# xr_vco_components_preroute3.net
KiCad netlist of a schematic drawn in EAGLE
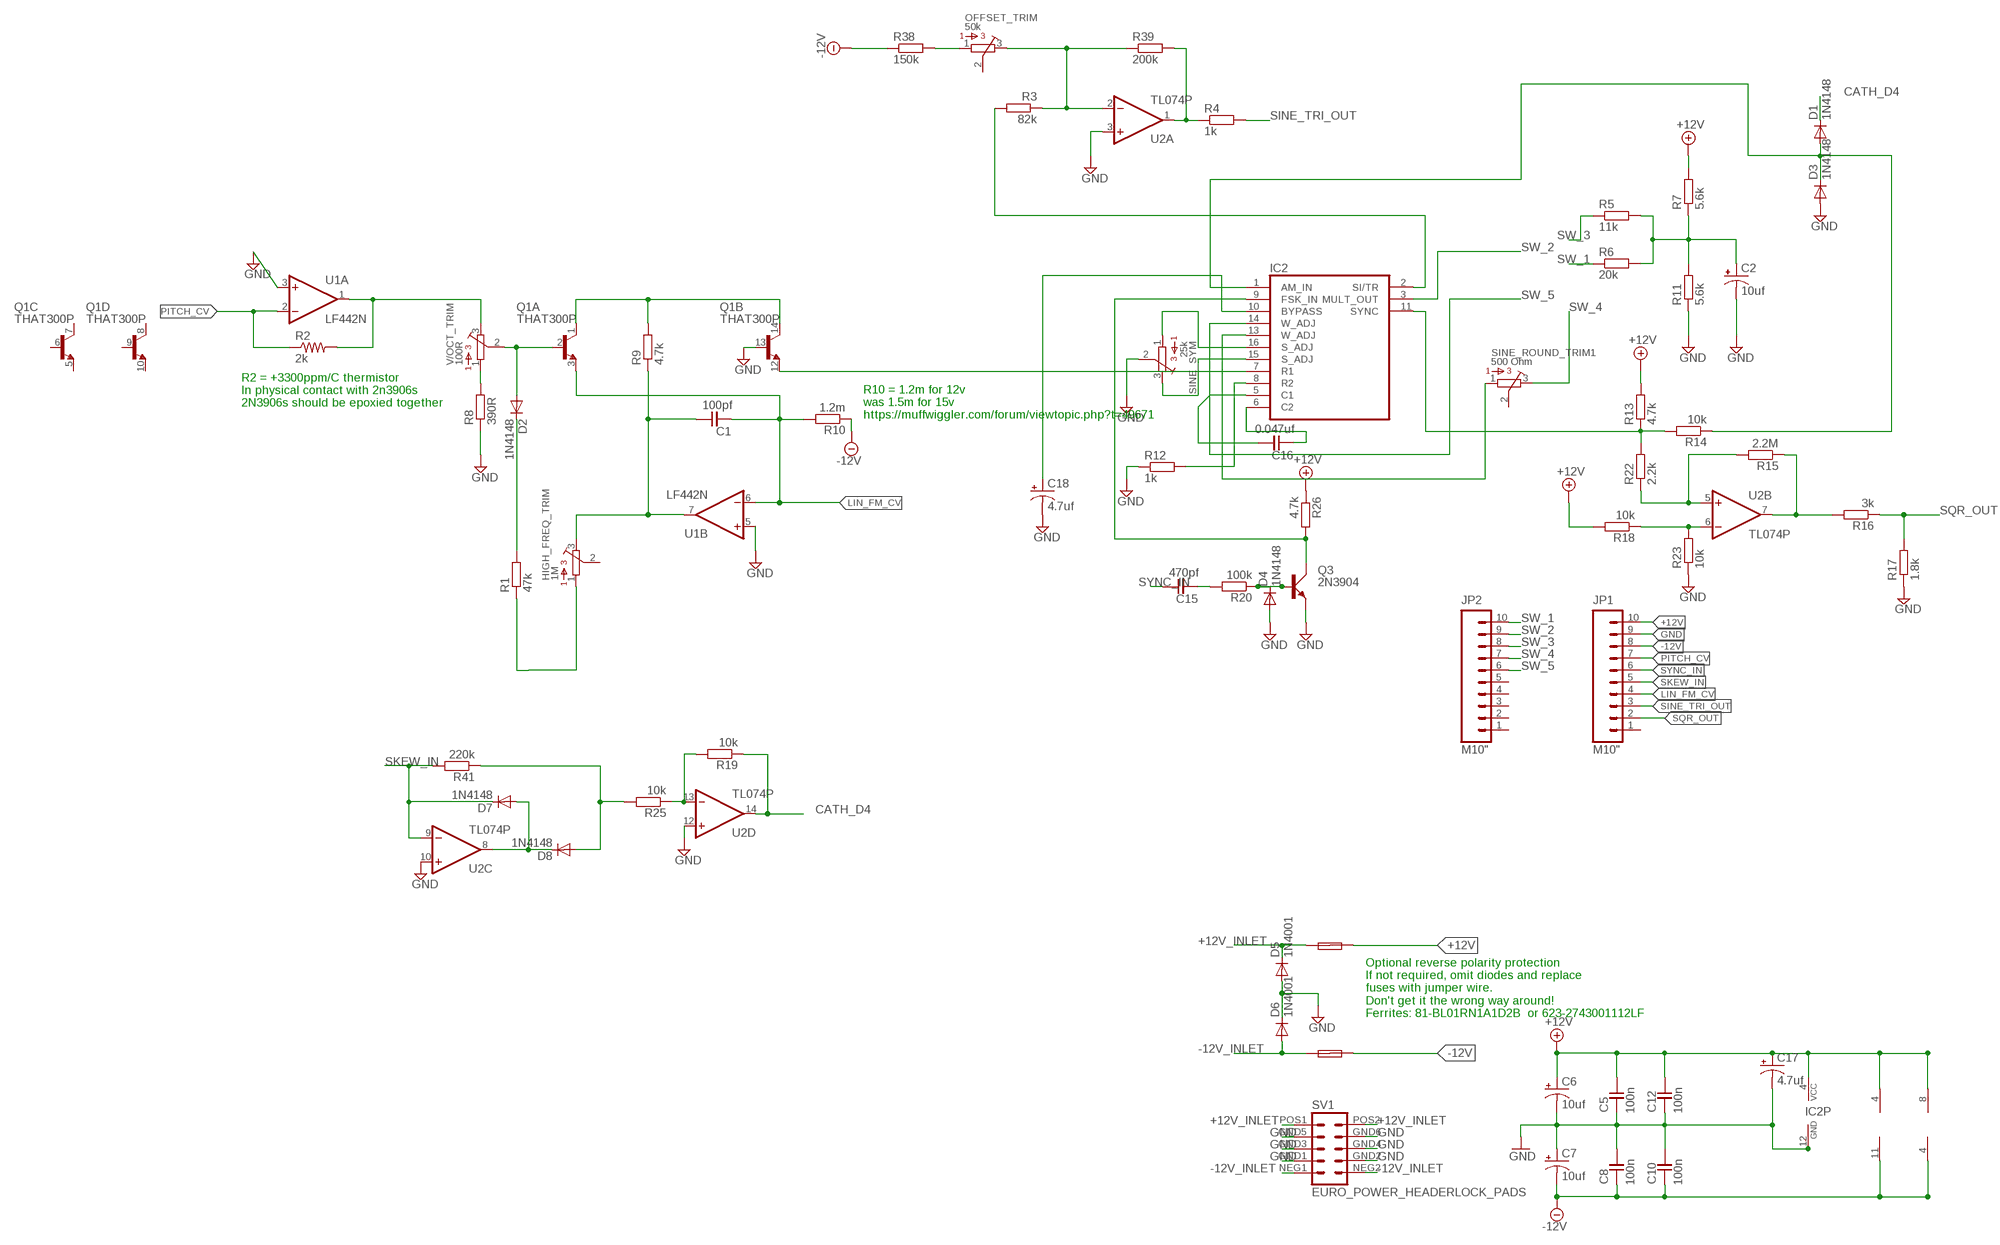
[diagram p0: schematic, sheet 1]

(export (version "E")
  (design (tool "Eeschema 10.0.6"))
  (components
    (comp (ref "C1")
      (value "100pf")
      (footprint "eagle-import:C050-024X044")
      (libsource (lib "eagle-import") (part "C-EU050-024X044"))
    )
    (comp (ref "C2")
      (value "10uf")
      (footprint "eagle-import:CPOL-RADIAL-10UF-25V")
      (libsource (lib "eagle-import") (part "CAP_POLPTH2"))
    )
    (comp (ref "C5")
      (value "100n")
      (footprint "eagle-import:C050-024X044")
      (libsource (lib "eagle-import") (part "C-EU050-024X044"))
    )
    (comp (ref "C6")
      (value "10uf")
      (footprint "eagle-import:CPOL-RADIAL-10UF-25V")
      (libsource (lib "eagle-import") (part "CAP_POLPTH2"))
    )
    (comp (ref "C7")
      (value "10uf")
      (footprint "eagle-import:CPOL-RADIAL-10UF-25V")
      (libsource (lib "eagle-import") (part "CAP_POLPTH2"))
    )
    (comp (ref "C8")
      (value "100n")
      (footprint "eagle-import:C050-024X044")
      (libsource (lib "eagle-import") (part "C-EU050-024X044"))
    )
    (comp (ref "C10")
      (value "100n")
      (footprint "eagle-import:C050-024X044")
      (libsource (lib "eagle-import") (part "C-EU050-024X044"))
    )
    (comp (ref "C12")
      (value "100n")
      (footprint "eagle-import:C050-024X044")
      (libsource (lib "eagle-import") (part "C-EU050-024X044"))
    )
    (comp (ref "C15")
      (value "470pf")
      (footprint "eagle-import:C050-024X044")
      (libsource (lib "eagle-import") (part "C-EU050-024X044"))
    )
    (comp (ref "C16")
      (value "0.047uf")
      (footprint "eagle-import:C050-024X044")
      (libsource (lib "eagle-import") (part "C-EU050-024X044"))
    )
    (comp (ref "C17")
      (value "4.7uf")
      (footprint "eagle-import:CPOL-RADIAL-10UF-25V")
      (libsource (lib "eagle-import") (part "CAP_POLPTH2"))
    )
    (comp (ref "C18")
      (value "4.7uf")
      (footprint "eagle-import:CPOL-RADIAL-10UF-25V")
      (libsource (lib "eagle-import") (part "CAP_POLPTH2"))
    )
    (comp (ref "D1")
      (value "1N4148")
      (footprint "eagle-import:DO35-7")
      (libsource (lib "eagle-import") (part "SMALL_DIODEDO35-7"))
    )
    (comp (ref "D2")
      (value "1N4148")
      (footprint "eagle-import:DO35-7")
      (libsource (lib "eagle-import") (part "SMALL_DIODEDO35-7"))
    )
    (comp (ref "D3")
      (value "1N4148")
      (footprint "eagle-import:DO35-7")
      (libsource (lib "eagle-import") (part "SMALL_DIODEDO35-7"))
    )
    (comp (ref "D4")
      (value "1N4148")
      (footprint "eagle-import:DO35-7")
      (libsource (lib "eagle-import") (part "SMALL_DIODEDO35-7"))
    )
    (comp (ref "D5")
      (value "1N4001")
      (footprint "eagle-import:DO41-10")
      (libsource (lib "eagle-import") (part "1N4004"))
    )
    (comp (ref "D6")
      (value "1N4001")
      (footprint "eagle-import:DO41-10")
      (libsource (lib "eagle-import") (part "1N4004"))
    )
    (comp (ref "D7")
      (value "1N4148")
      (footprint "eagle-import:DO35-7")
      (libsource (lib "eagle-import") (part "SMALL_DIODEDO35-7"))
    )
    (comp (ref "D8")
      (value "1N4148")
      (footprint "eagle-import:DO35-7")
      (libsource (lib "eagle-import") (part "SMALL_DIODEDO35-7"))
    )
    (comp (ref "F1")
      (value "FUSE")
      (footprint "eagle-import:C050H075X075")
      (libsource (lib "eagle-import") (part "PTC_FUSEPOLY_FUSE"))
    )
    (comp (ref "F2")
      (value "FUSE")
      (footprint "eagle-import:C050H075X075")
      (libsource (lib "eagle-import") (part "PTC_FUSEPOLY_FUSE"))
    )
    (comp (ref "HIGH_FREQ_TRIM")
      (value "1M")
      (footprint "eagle-import:BOURNS_3362P_TRIMMER")
      (libsource (lib "eagle-import") (part "BOURNS_3362P_TRIMMERP"))
    )
    (comp (ref "IC2")
      (value "XR-2206")
      (footprint "eagle-import:DIL16")
      (libsource (lib "eagle-import") (part "XR-2206"))
    )
    (comp (ref "JP1")
      (value "M10\"")
      (footprint "eagle-import:1X10")
      (libsource (lib "eagle-import") (part "M10{dblquote}"))
    )
    (comp (ref "JP2")
      (value "M10\"")
      (footprint "eagle-import:1X10")
      (libsource (lib "eagle-import") (part "M10{dblquote}"))
    )
    (comp (ref "OFFSET_TRIM")
      (value "50k")
      (footprint "eagle-import:BOURNS_3362P_TRIMMER")
      (libsource (lib "eagle-import") (part "BOURNS_3362P_TRIMMERP"))
    )
    (comp (ref "Q1")
      (value "THAT300P")
      (footprint "eagle-import:DIL14")
      (libsource (lib "eagle-import") (part "THAT300P"))
    )
    (comp (ref "Q3")
      (value "2N3904")
      (footprint "eagle-import:TO92D")
      (libsource (lib "eagle-import") (part "2N3904"))
    )
    (comp (ref "R1")
      (value "47k")
      (footprint "eagle-import:7MM_RESISTOR")
      (libsource (lib "eagle-import") (part "RESISTOR7MM"))
    )
    (comp (ref "R2")
      (value "2k")
      (footprint "eagle-import:0309_12")
      (libsource (lib "eagle-import") (part "R-US_0309/12"))
    )
    (comp (ref "R3")
      (value "82k")
      (footprint "eagle-import:7MM_RESISTOR")
      (libsource (lib "eagle-import") (part "RESISTOR7MM"))
    )
    (comp (ref "R4")
      (value "1k")
      (footprint "eagle-import:7MM_RESISTOR")
      (libsource (lib "eagle-import") (part "RESISTOR7MM"))
    )
    (comp (ref "R5")
      (value "11k")
      (footprint "eagle-import:7MM_RESISTOR")
      (libsource (lib "eagle-import") (part "RESISTOR7MM"))
    )
    (comp (ref "R6")
      (value "20k")
      (footprint "eagle-import:7MM_RESISTOR")
      (libsource (lib "eagle-import") (part "RESISTOR7MM"))
    )
    (comp (ref "R7")
      (value "5.6k")
      (footprint "eagle-import:7MM_RESISTOR")
      (libsource (lib "eagle-import") (part "RESISTOR7MM"))
    )
    (comp (ref "R8")
      (value "390R")
      (footprint "eagle-import:7MM_RESISTOR")
      (libsource (lib "eagle-import") (part "RESISTOR7MM"))
    )
    (comp (ref "R9")
      (value "4.7k")
      (footprint "eagle-import:7MM_RESISTOR")
      (libsource (lib "eagle-import") (part "RESISTOR7MM"))
    )
    (comp (ref "R10")
      (value "1.2m")
      (footprint "eagle-import:7MM_RESISTOR")
      (libsource (lib "eagle-import") (part "RESISTOR7MM"))
    )
    (comp (ref "R11")
      (value "5.6k")
      (footprint "eagle-import:7MM_RESISTOR")
      (libsource (lib "eagle-import") (part "RESISTOR7MM"))
    )
    (comp (ref "R12")
      (value "1k")
      (footprint "eagle-import:7MM_RESISTOR")
      (libsource (lib "eagle-import") (part "RESISTOR7MM"))
    )
    (comp (ref "R13")
      (value "4.7k")
      (footprint "eagle-import:7MM_RESISTOR")
      (libsource (lib "eagle-import") (part "RESISTOR7MM"))
    )
    (comp (ref "R14")
      (value "10k")
      (footprint "eagle-import:7MM_RESISTOR")
      (libsource (lib "eagle-import") (part "RESISTOR7MM"))
    )
    (comp (ref "R15")
      (value "2.2M")
      (footprint "eagle-import:7MM_RESISTOR")
      (libsource (lib "eagle-import") (part "RESISTOR7MM"))
    )
    (comp (ref "R16")
      (value "3k")
      (footprint "eagle-import:7MM_RESISTOR")
      (libsource (lib "eagle-import") (part "RESISTOR7MM"))
    )
    (comp (ref "R17")
      (value "1.8k")
      (footprint "eagle-import:7MM_RESISTOR")
      (libsource (lib "eagle-import") (part "RESISTOR7MM"))
    )
    (comp (ref "R18")
      (value "10k")
      (footprint "eagle-import:7MM_RESISTOR")
      (libsource (lib "eagle-import") (part "RESISTOR7MM"))
    )
    (comp (ref "R19")
      (value "10k")
      (footprint "eagle-import:7MM_RESISTOR")
      (libsource (lib "eagle-import") (part "RESISTOR7MM"))
    )
    (comp (ref "R20")
      (value "100k")
      (footprint "eagle-import:7MM_RESISTOR")
      (libsource (lib "eagle-import") (part "RESISTOR7MM"))
    )
    (comp (ref "R22")
      (value "2.2k")
      (footprint "eagle-import:7MM_RESISTOR")
      (libsource (lib "eagle-import") (part "RESISTOR7MM"))
    )
    (comp (ref "R23")
      (value "10k")
      (footprint "eagle-import:7MM_RESISTOR")
      (libsource (lib "eagle-import") (part "RESISTOR7MM"))
    )
    (comp (ref "R25")
      (value "10k")
      (footprint "eagle-import:7MM_RESISTOR")
      (libsource (lib "eagle-import") (part "RESISTOR7MM"))
    )
    (comp (ref "R26")
      (value "4.7k")
      (footprint "eagle-import:7MM_RESISTOR")
      (libsource (lib "eagle-import") (part "RESISTOR7MM"))
    )
    (comp (ref "R38")
      (value "150k")
      (footprint "eagle-import:7MM_RESISTOR")
      (libsource (lib "eagle-import") (part "RESISTOR7MM"))
    )
    (comp (ref "R39")
      (value "200k")
      (footprint "eagle-import:7MM_RESISTOR")
      (libsource (lib "eagle-import") (part "RESISTOR7MM"))
    )
    (comp (ref "R41")
      (value "220k")
      (footprint "eagle-import:7MM_RESISTOR")
      (libsource (lib "eagle-import") (part "RESISTOR7MM"))
    )
    (comp (ref "SINE_ROUND_TRIM1")
      (value "500 Ohm")
      (footprint "eagle-import:BOURNS_3362P_TRIMMER")
      (libsource (lib "eagle-import") (part "BOURNS_3362P_TRIMMERP"))
    )
    (comp (ref "SINE_SYM")
      (value "25k")
      (footprint "eagle-import:BOURNS_3362P_TRIMMER")
      (libsource (lib "eagle-import") (part "BOURNS_3362P_TRIMMERP"))
    )
    (comp (ref "SV1")
      (value "EURO_POWER_HEADERLOCK_PADS")
      (footprint "eagle-import:EURO_PWR_HEADER_LOCK")
      (libsource (lib "eagle-import") (part "EURO_POWER_HEADERLOCK_PADS"))
    )
    (comp (ref "U1")
      (value "LF442N")
      (footprint "eagle-import:DIL08")
      (libsource (lib "eagle-import") (part "LF442N"))
    )
    (comp (ref "U2")
      (value "TL074P")
      (footprint "eagle-import:DIL14")
      (libsource (lib "eagle-import") (part "TL074P"))
    )
    (comp (ref "V/OCT_TRIM")
      (value "100R")
      (footprint "eagle-import:BOURNS_3362P_TRIMMER")
      (libsource (lib "eagle-import") (part "BOURNS_3362P_TRIMMERP"))
    )
  )
  (nets
    (net (code "1") (name "+12V") (class "Default")
      (node (ref "C12") (pin "1") (pinfunction "1_1") (pintype "passive"))
      (node (ref "C17") (pin "1") (pinfunction "+_1") (pintype "passive"))
      (node (ref "C5") (pin "1") (pinfunction "1_1") (pintype "passive"))
      (node (ref "C6") (pin "1") (pinfunction "+_1") (pintype "passive"))
      (node (ref "F1") (pin "2") (pinfunction "P$2_2") (pintype "bidirectional"))
      (node (ref "IC2") (pin "4") (pinfunction "VCC_4") (pintype "power_in"))
      (node (ref "JP1") (pin "10") (pinfunction "10_10") (pintype "passive"))
      (node (ref "R13") (pin "2") (pinfunction "2_2") (pintype "passive"))
      (node (ref "R18") (pin "2") (pinfunction "2_2") (pintype "passive"))
      (node (ref "R26") (pin "1") (pinfunction "1_1") (pintype "passive"))
      (node (ref "R7") (pin "2") (pinfunction "2_2") (pintype "passive"))
      (node (ref "U1") (pin "8") (pinfunction "V+_8") (pintype "power_in"))
      (node (ref "U2") (pin "4") (pinfunction "V+_4") (pintype "power_in"))
    )
    (net (code "2") (name "-12V") (class "Default")
      (node (ref "C10") (pin "2") (pinfunction "2_2") (pintype "passive"))
      (node (ref "C7") (pin "2") (pinfunction "-_2") (pintype "passive"))
      (node (ref "C8") (pin "2") (pinfunction "2_2") (pintype "passive"))
      (node (ref "F2") (pin "2") (pinfunction "P$2_2") (pintype "bidirectional"))
      (node (ref "JP1") (pin "8") (pinfunction "8_8") (pintype "passive"))
      (node (ref "R10") (pin "1") (pinfunction "1_1") (pintype "passive"))
      (node (ref "R38") (pin "1") (pinfunction "1_1") (pintype "passive"))
      (node (ref "U1") (pin "4") (pinfunction "V-_4") (pintype "power_in"))
      (node (ref "U2") (pin "11") (pinfunction "V-_11") (pintype "power_in"))
    )
    (net (code "3") (name "/+12V_INLET") (class "Default")
      (node (ref "D5") (pin "C") (pinfunction "C_C") (pintype "passive"))
      (node (ref "F1") (pin "1") (pinfunction "P$1_1") (pintype "bidirectional"))
      (node (ref "SV1") (pin "POS1") (pinfunction "10_POS1") (pintype "passive"))
      (node (ref "SV1") (pin "POS2") (pinfunction "9_POS2") (pintype "passive"))
    )
    (net (code "4") (name "/-12V_INLET") (class "Default")
      (node (ref "D6") (pin "A") (pinfunction "A_A") (pintype "passive"))
      (node (ref "F2") (pin "1") (pinfunction "P$1_1") (pintype "bidirectional"))
      (node (ref "SV1") (pin "NEG1") (pinfunction "2_NEG1") (pintype "passive"))
      (node (ref "SV1") (pin "NEG2") (pinfunction "1_NEG2") (pintype "passive"))
    )
    (net (code "5") (name "/CATH_D4") (class "Default")
      (node (ref "D1") (pin "C") (pinfunction "C_C") (pintype "passive"))
      (node (ref "R19") (pin "1") (pinfunction "1_1") (pintype "passive"))
      (node (ref "U2") (pin "14") (pinfunction "OUT_14") (pintype "output"))
    )
    (net (code "6") (name "/SW_1") (class "Default")
      (node (ref "JP2") (pin "10") (pinfunction "10_10") (pintype "passive"))
      (node (ref "R6") (pin "1") (pinfunction "1_1") (pintype "passive"))
    )
    (net (code "7") (name "/SW_2") (class "Default")
      (node (ref "IC2") (pin "3") (pinfunction "MULT_OUT_3") (pintype "output"))
      (node (ref "JP2") (pin "9") (pinfunction "9_9") (pintype "passive"))
    )
    (net (code "8") (name "/SW_3") (class "Default")
      (node (ref "JP2") (pin "8") (pinfunction "8_8") (pintype "passive"))
      (node (ref "R5") (pin "1") (pinfunction "1_1") (pintype "passive"))
    )
    (net (code "9") (name "/SW_4") (class "Default")
      (node (ref "JP2") (pin "7") (pinfunction "7_7") (pintype "passive"))
      (node (ref "SINE_ROUND_TRIM1") (pin "3") (pinfunction "3_3") (pintype "passive"))
    )
    (net (code "10") (name "/SW_5") (class "Default")
      (node (ref "IC2") (pin "14") (pinfunction "W_ADJ_14") (pintype "input"))
      (node (ref "JP2") (pin "6") (pinfunction "6_6") (pintype "passive"))
    )
    (net (code "11") (name "GND") (class "Default")
      (node (ref "C10") (pin "1") (pinfunction "1_1") (pintype "passive"))
      (node (ref "C12") (pin "2") (pinfunction "2_2") (pintype "passive"))
      (node (ref "C17") (pin "2") (pinfunction "-_2") (pintype "passive"))
      (node (ref "C18") (pin "2") (pinfunction "-_2") (pintype "passive"))
      (node (ref "C2") (pin "2") (pinfunction "-_2") (pintype "passive"))
      (node (ref "C5") (pin "2") (pinfunction "2_2") (pintype "passive"))
      (node (ref "C6") (pin "2") (pinfunction "-_2") (pintype "passive"))
      (node (ref "C7") (pin "1") (pinfunction "+_1") (pintype "passive"))
      (node (ref "C8") (pin "1") (pinfunction "1_1") (pintype "passive"))
      (node (ref "D3") (pin "A") (pinfunction "A_A") (pintype "passive"))
      (node (ref "D4") (pin "A") (pinfunction "A_A") (pintype "passive"))
      (node (ref "D5") (pin "A") (pinfunction "A_A") (pintype "passive"))
      (node (ref "D6") (pin "C") (pinfunction "C_C") (pintype "passive"))
      (node (ref "IC2") (pin "12") (pinfunction "GND_12") (pintype "power_in"))
      (node (ref "JP1") (pin "9") (pinfunction "9_9") (pintype "passive"))
      (node (ref "Q1") (pin "13") (pinfunction "B_13") (pintype "passive"))
      (node (ref "Q3") (pin "E") (pinfunction "E_E") (pintype "passive"))
      (node (ref "R11") (pin "1") (pinfunction "1_1") (pintype "passive"))
      (node (ref "R12") (pin "1") (pinfunction "1_1") (pintype "passive"))
      (node (ref "R17") (pin "1") (pinfunction "1_1") (pintype "passive"))
      (node (ref "R23") (pin "1") (pinfunction "1_1") (pintype "passive"))
      (node (ref "R8") (pin "1") (pinfunction "1_1") (pintype "passive"))
      (node (ref "SINE_SYM") (pin "2") (pinfunction "2_2") (pintype "passive"))
      (node (ref "SV1") (pin "GND1") (pinfunction "4_GND1") (pintype "passive"))
      (node (ref "SV1") (pin "GND2") (pinfunction "3_GND2") (pintype "passive"))
      (node (ref "SV1") (pin "GND3") (pinfunction "6_GND3") (pintype "passive"))
      (node (ref "SV1") (pin "GND4") (pinfunction "5_GND4") (pintype "passive"))
      (node (ref "SV1") (pin "GND5") (pinfunction "8_GND5") (pintype "passive"))
      (node (ref "SV1") (pin "GND6") (pinfunction "7_GND6") (pintype "passive"))
      (node (ref "U1") (pin "3") (pinfunction "+IN_3") (pintype "input"))
      (node (ref "U1") (pin "5") (pinfunction "+IN_5") (pintype "input"))
      (node (ref "U2") (pin "10") (pinfunction "+IN_10") (pintype "input"))
      (node (ref "U2") (pin "12") (pinfunction "+IN_12") (pintype "input"))
      (node (ref "U2") (pin "3") (pinfunction "+IN_3") (pintype "input"))
    )
    (net (code "12") (name "LIN_FM_CV") (class "Default")
      (node (ref "C1") (pin "2") (pinfunction "2_2") (pintype "passive"))
      (node (ref "JP1") (pin "4") (pinfunction "4_4") (pintype "passive"))
      (node (ref "Q1") (pin "3") (pinfunction "E_3") (pintype "passive"))
      (node (ref "R10") (pin "2") (pinfunction "2_2") (pintype "passive"))
      (node (ref "U1") (pin "6") (pinfunction "-IN_6") (pintype "input"))
    )
    (net (code "13") (name "Net-(C2-+)") (class "Default")
      (node (ref "C2") (pin "1") (pinfunction "+_1") (pintype "passive"))
      (node (ref "R11") (pin "2") (pinfunction "2_2") (pintype "passive"))
      (node (ref "R5") (pin "2") (pinfunction "2_2") (pintype "passive"))
      (node (ref "R6") (pin "2") (pinfunction "2_2") (pintype "passive"))
      (node (ref "R7") (pin "1") (pinfunction "1_1") (pintype "passive"))
    )
    (net (code "14") (name "Net-(C15-Pad2)") (class "Default")
      (node (ref "C15") (pin "2") (pinfunction "2_2") (pintype "passive"))
      (node (ref "R20") (pin "2") (pinfunction "2_2") (pintype "passive"))
    )
    (net (code "15") (name "Net-(C18-+)") (class "Default")
      (node (ref "C18") (pin "1") (pinfunction "+_1") (pintype "passive"))
      (node (ref "IC2") (pin "10") (pinfunction "BYPASS_10") (pintype "input"))
    )
    (net (code "16") (name "Net-(D2-PadC)") (class "Default")
      (node (ref "D2") (pin "C") (pinfunction "C_C") (pintype "passive"))
      (node (ref "R1") (pin "2") (pinfunction "2_2") (pintype "passive"))
    )
    (net (code "17") (name "Net-(D4-PadC)") (class "Default")
      (node (ref "D4") (pin "C") (pinfunction "C_C") (pintype "passive"))
      (node (ref "Q3") (pin "B") (pinfunction "B_B") (pintype "passive"))
      (node (ref "R20") (pin "1") (pinfunction "1_1") (pintype "passive"))
    )
    (net (code "18") (name "Net-(D8-PadA)") (class "Default")
      (node (ref "D8") (pin "A") (pinfunction "A_A") (pintype "passive"))
      (node (ref "R25") (pin "2") (pinfunction "2_2") (pintype "passive"))
      (node (ref "R41") (pin "1") (pinfunction "1_1") (pintype "passive"))
    )
    (net (code "19") (name "Net-(HIGH_FREQ_TRIM-Pad1)") (class "Default")
      (node (ref "HIGH_FREQ_TRIM") (pin "1") (pinfunction "1_1") (pintype "passive"))
      (node (ref "R1") (pin "1") (pinfunction "1_1") (pintype "passive"))
    )
    (net (code "20") (name "Net-(IC2A-AM_IN)") (class "Default")
      (node (ref "D1") (pin "A") (pinfunction "A_A") (pintype "passive"))
      (node (ref "D3") (pin "C") (pinfunction "C_C") (pintype "passive"))
      (node (ref "IC2") (pin "1") (pinfunction "AM_IN_1") (pintype "input"))
      (node (ref "R14") (pin "1") (pinfunction "1_1") (pintype "passive"))
    )
    (net (code "21") (name "Net-(IC2A-C1)") (class "Default")
      (node (ref "C16") (pin "1") (pinfunction "1_1") (pintype "passive"))
      (node (ref "IC2") (pin "5") (pinfunction "C1_5") (pintype "input"))
    )
    (net (code "22") (name "Net-(IC2A-C2)") (class "Default")
      (node (ref "C16") (pin "2") (pinfunction "2_2") (pintype "passive"))
      (node (ref "IC2") (pin "6") (pinfunction "C2_6") (pintype "input"))
    )
    (net (code "23") (name "Net-(IC2A-FSK_IN)") (class "Default")
      (node (ref "IC2") (pin "9") (pinfunction "FSK_IN_9") (pintype "input"))
      (node (ref "Q3") (pin "C") (pinfunction "C_C") (pintype "passive"))
      (node (ref "R26") (pin "2") (pinfunction "2_2") (pintype "passive"))
    )
    (net (code "24") (name "Net-(IC2A-R1)") (class "Default")
      (node (ref "IC2") (pin "7") (pinfunction "R1_7") (pintype "input"))
      (node (ref "Q1") (pin "12") (pinfunction "E_12") (pintype "passive"))
    )
    (net (code "25") (name "Net-(IC2A-R2)") (class "Default")
      (node (ref "IC2") (pin "8") (pinfunction "R2_8") (pintype "input"))
      (node (ref "R12") (pin "2") (pinfunction "2_2") (pintype "passive"))
    )
    (net (code "26") (name "Net-(IC2A-SI{slash}TR)") (class "Default")
      (node (ref "IC2") (pin "2") (pinfunction "SI/TR_2") (pintype "output"))
      (node (ref "R3") (pin "2") (pinfunction "2_2") (pintype "passive"))
    )
    (net (code "27") (name "Net-(IC2A-SYNC)") (class "Default")
      (node (ref "IC2") (pin "11") (pinfunction "SYNC_11") (pintype "output"))
      (node (ref "R13") (pin "1") (pinfunction "1_1") (pintype "passive"))
      (node (ref "R14") (pin "2") (pinfunction "2_2") (pintype "passive"))
      (node (ref "R22") (pin "2") (pinfunction "2_2") (pintype "passive"))
    )
    (net (code "28") (name "Net-(IC2A-S_ADJ-Pad15)") (class "Default")
      (node (ref "IC2") (pin "15") (pinfunction "S_ADJ_15") (pintype "input"))
      (node (ref "SINE_SYM") (pin "3") (pinfunction "3_3") (pintype "passive"))
    )
    (net (code "29") (name "Net-(IC2A-S_ADJ-Pad16)") (class "Default")
      (node (ref "IC2") (pin "16") (pinfunction "S_ADJ_16") (pintype "input"))
      (node (ref "SINE_SYM") (pin "1") (pinfunction "1_1") (pintype "passive"))
    )
    (net (code "30") (name "Net-(IC2A-W_ADJ-Pad13)") (class "Default")
      (node (ref "IC2") (pin "13") (pinfunction "W_ADJ_13") (pintype "input"))
      (node (ref "SINE_ROUND_TRIM1") (pin "1") (pinfunction "1_1") (pintype "passive"))
    )
    (net (code "31") (name "Net-(OFFSET_TRIM-Pad1)") (class "Default")
      (node (ref "OFFSET_TRIM") (pin "1") (pinfunction "1_1") (pintype "passive"))
      (node (ref "R38") (pin "2") (pinfunction "2_2") (pintype "passive"))
    )
    (net (code "32") (name "Net-(Q1A-B)") (class "Default")
      (node (ref "D2") (pin "A") (pinfunction "A_A") (pintype "passive"))
      (node (ref "Q1") (pin "2") (pinfunction "B_2") (pintype "passive"))
      (node (ref "V/OCT_TRIM") (pin "2") (pinfunction "2_2") (pintype "passive"))
    )
    (net (code "33") (name "Net-(Q1A-C)") (class "Default")
      (node (ref "Q1") (pin "1") (pinfunction "C_1") (pintype "passive"))
      (node (ref "Q1") (pin "14") (pinfunction "C_14") (pintype "passive"))
      (node (ref "R9") (pin "2") (pinfunction "2_2") (pintype "passive"))
    )
    (net (code "34") (name "Net-(R8-Pad2)") (class "Default")
      (node (ref "R8") (pin "2") (pinfunction "2_2") (pintype "passive"))
      (node (ref "V/OCT_TRIM") (pin "1") (pinfunction "1_1") (pintype "passive"))
    )
    (net (code "35") (name "Net-(U1A-OUT)") (class "Default")
      (node (ref "R2") (pin "2") (pinfunction "2_2") (pintype "passive"))
      (node (ref "U1") (pin "1") (pinfunction "OUT_1") (pintype "output"))
      (node (ref "V/OCT_TRIM") (pin "3") (pinfunction "3_3") (pintype "passive"))
    )
    (net (code "36") (name "Net-(U1B-OUT)") (class "Default")
      (node (ref "C1") (pin "1") (pinfunction "1_1") (pintype "passive"))
      (node (ref "HIGH_FREQ_TRIM") (pin "3") (pinfunction "3_3") (pintype "passive"))
      (node (ref "R9") (pin "1") (pinfunction "1_1") (pintype "passive"))
      (node (ref "U1") (pin "7") (pinfunction "OUT_7") (pintype "output"))
    )
    (net (code "37") (name "Net-(U2A--IN)") (class "Default")
      (node (ref "OFFSET_TRIM") (pin "3") (pinfunction "3_3") (pintype "passive"))
      (node (ref "R3") (pin "1") (pinfunction "1_1") (pintype "passive"))
      (node (ref "R39") (pin "1") (pinfunction "1_1") (pintype "passive"))
      (node (ref "U2") (pin "2") (pinfunction "-IN_2") (pintype "input"))
    )
    (net (code "38") (name "Net-(U2A-OUT)") (class "Default")
      (node (ref "R39") (pin "2") (pinfunction "2_2") (pintype "passive"))
      (node (ref "R4") (pin "1") (pinfunction "1_1") (pintype "passive"))
      (node (ref "U2") (pin "1") (pinfunction "OUT_1") (pintype "output"))
    )
    (net (code "39") (name "Net-(U2B-+IN)") (class "Default")
      (node (ref "R15") (pin "2") (pinfunction "2_2") (pintype "passive"))
      (node (ref "R22") (pin "1") (pinfunction "1_1") (pintype "passive"))
      (node (ref "U2") (pin "5") (pinfunction "+IN_5") (pintype "input"))
    )
    (net (code "40") (name "Net-(U2B--IN)") (class "Default")
      (node (ref "R18") (pin "1") (pinfunction "1_1") (pintype "passive"))
      (node (ref "R23") (pin "2") (pinfunction "2_2") (pintype "passive"))
      (node (ref "U2") (pin "6") (pinfunction "-IN_6") (pintype "input"))
    )
    (net (code "41") (name "Net-(U2B-OUT)") (class "Default")
      (node (ref "R15") (pin "1") (pinfunction "1_1") (pintype "passive"))
      (node (ref "R16") (pin "2") (pinfunction "2_2") (pintype "passive"))
      (node (ref "U2") (pin "7") (pinfunction "OUT_7") (pintype "output"))
    )
    (net (code "42") (name "Net-(U2C-OUT)") (class "Default")
      (node (ref "D7") (pin "A") (pinfunction "A_A") (pintype "passive"))
      (node (ref "D8") (pin "C") (pinfunction "C_C") (pintype "passive"))
      (node (ref "U2") (pin "8") (pinfunction "OUT_8") (pintype "output"))
    )
    (net (code "43") (name "Net-(U2D--IN)") (class "Default")
      (node (ref "R19") (pin "2") (pinfunction "2_2") (pintype "passive"))
      (node (ref "R25") (pin "1") (pinfunction "1_1") (pintype "passive"))
      (node (ref "U2") (pin "13") (pinfunction "-IN_13") (pintype "input"))
    )
    (net (code "44") (name "PITCH_CV") (class "Default")
      (node (ref "JP1") (pin "7") (pinfunction "7_7") (pintype "passive"))
      (node (ref "R2") (pin "1") (pinfunction "1_1") (pintype "passive"))
      (node (ref "U1") (pin "2") (pinfunction "-IN_2") (pintype "input"))
    )
    (net (code "45") (name "SINE_TRI_OUT") (class "Default")
      (node (ref "JP1") (pin "3") (pinfunction "3_3") (pintype "passive"))
      (node (ref "R4") (pin "2") (pinfunction "2_2") (pintype "passive"))
    )
    (net (code "46") (name "SKEW_IN") (class "Default")
      (node (ref "D7") (pin "C") (pinfunction "C_C") (pintype "passive"))
      (node (ref "JP1") (pin "5") (pinfunction "5_5") (pintype "passive"))
      (node (ref "R41") (pin "2") (pinfunction "2_2") (pintype "passive"))
      (node (ref "U2") (pin "9") (pinfunction "-IN_9") (pintype "input"))
    )
    (net (code "47") (name "SQR_OUT") (class "Default")
      (node (ref "JP1") (pin "2") (pinfunction "2_2") (pintype "passive"))
      (node (ref "R16") (pin "1") (pinfunction "1_1") (pintype "passive"))
      (node (ref "R17") (pin "2") (pinfunction "2_2") (pintype "passive"))
    )
    (net (code "48") (name "SYNC_IN") (class "Default")
      (node (ref "C15") (pin "1") (pinfunction "1_1") (pintype "passive"))
      (node (ref "JP1") (pin "6") (pinfunction "6_6") (pintype "passive"))
    )
    (net (code "49") (name "unconnected-(HIGH_FREQ_TRIM-Pad2)") (class "Default")
      (node (ref "HIGH_FREQ_TRIM") (pin "2") (pinfunction "2_2") (pintype "passive"))
    )
    (net (code "50") (name "unconnected-(JP1-Pad1)") (class "Default")
      (node (ref "JP1") (pin "1") (pinfunction "1_1") (pintype "passive"))
    )
    (net (code "51") (name "unconnected-(JP2-Pad1)") (class "Default")
      (node (ref "JP2") (pin "1") (pinfunction "1_1") (pintype "passive"))
    )
    (net (code "52") (name "unconnected-(JP2-Pad2)") (class "Default")
      (node (ref "JP2") (pin "2") (pinfunction "2_2") (pintype "passive"))
    )
    (net (code "53") (name "unconnected-(JP2-Pad3)") (class "Default")
      (node (ref "JP2") (pin "3") (pinfunction "3_3") (pintype "passive"))
    )
    (net (code "54") (name "unconnected-(JP2-Pad4)") (class "Default")
      (node (ref "JP2") (pin "4") (pinfunction "4_4") (pintype "passive"))
    )
    (net (code "55") (name "unconnected-(JP2-Pad5)") (class "Default")
      (node (ref "JP2") (pin "5") (pinfunction "5_5") (pintype "passive"))
    )
    (net (code "56") (name "unconnected-(OFFSET_TRIM-Pad2)") (class "Default")
      (node (ref "OFFSET_TRIM") (pin "2") (pinfunction "2_2") (pintype "passive"))
    )
    (net (code "57") (name "unconnected-(Q1C-B-Pad6)") (class "Default")
      (node (ref "Q1") (pin "6") (pinfunction "B_6") (pintype "passive"))
    )
    (net (code "58") (name "unconnected-(Q1C-C-Pad7)") (class "Default")
      (node (ref "Q1") (pin "7") (pinfunction "C_7") (pintype "passive"))
    )
    (net (code "59") (name "unconnected-(Q1C-E-Pad5)") (class "Default")
      (node (ref "Q1") (pin "5") (pinfunction "E_5") (pintype "passive"))
    )
    (net (code "60") (name "unconnected-(Q1D-B-Pad9)") (class "Default")
      (node (ref "Q1") (pin "9") (pinfunction "B_9") (pintype "passive"))
    )
    (net (code "61") (name "unconnected-(Q1D-C-Pad8)") (class "Default")
      (node (ref "Q1") (pin "8") (pinfunction "C_8") (pintype "passive"))
    )
    (net (code "62") (name "unconnected-(Q1D-E-Pad10)") (class "Default")
      (node (ref "Q1") (pin "10") (pinfunction "E_10") (pintype "passive"))
    )
    (net (code "63") (name "unconnected-(SINE_ROUND_TRIM1-Pad2)") (class "Default")
      (node (ref "SINE_ROUND_TRIM1") (pin "2") (pinfunction "2_2") (pintype "passive"))
    )
  )
)
